# FPGA_Bypass_3V3.net
KiCad netlist of a schematic drawn in Altium Designer
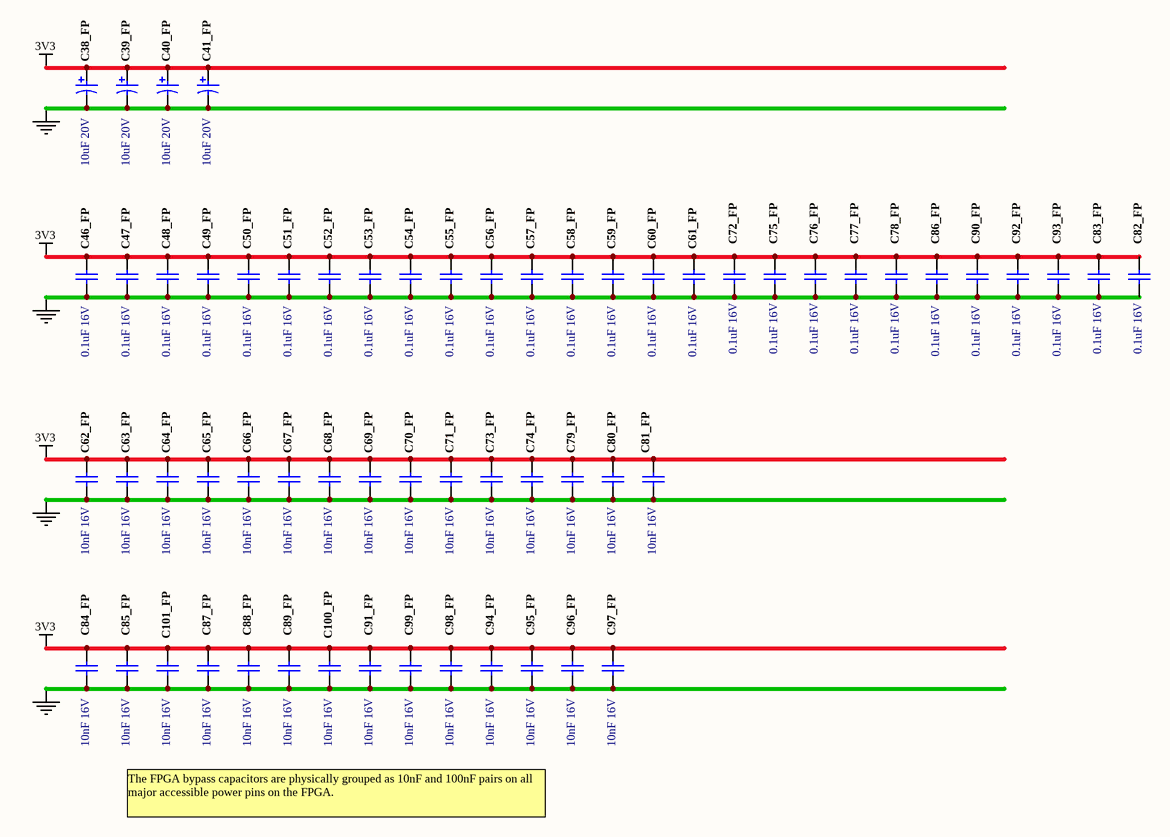
[diagram p0: FPGA_Bypass_3V3.SCHDOC]

(export (version "E")
  (design (tool "Eeschema 10.0.6"))
  (components
    (comp (ref "C38_FP")
      (value "10uF 20V")
      (footprint "CAPC3528-STAR")
      (description "Capacitor, Tantalum, 10uF 10% 20V MCCT-B (3528)")
      (fields (field (name "TOLERANCE") "10 %"))
      (libsource (lib "altium-import") (part "root_0_CAP-P_"))
    )
    (comp (ref "C39_FP")
      (value "10uF 20V")
      (footprint "CAPC3528-STAR")
      (description "Capacitor, Tantalum, 10uF 10% 20V MCCT-B (3528)")
      (fields (field (name "TOLERANCE") "10 %"))
      (libsource (lib "altium-import") (part "root_0_CAP-P_"))
    )
    (comp (ref "C40_FP")
      (value "10uF 20V")
      (footprint "CAPC3528-STAR")
      (description "Capacitor, Tantalum, 10uF 10% 20V MCCT-B (3528)")
      (fields (field (name "TOLERANCE") "10 %"))
      (libsource (lib "altium-import") (part "root_0_CAP-P_"))
    )
    (comp (ref "C41_FP")
      (value "10uF 20V")
      (footprint "CAPC3528-STAR")
      (description "Capacitor, Tantalum, 10uF 10% 20V MCCT-B (3528)")
      (fields (field (name "TOLERANCE") "10 %"))
      (libsource (lib "altium-import") (part "root_0_CAP-P_"))
    )
    (comp (ref "C46_FP")
      (value "0.1uF 16V")
      (footprint "CAPC1005-STAR")
      (description "Capacitor, Ceramic, 0.1uF 10% 16V 0402 (1005) X7R")
      (fields (field (name "TOLERANCE") "10 %"))
      (libsource (lib "altium-import") (part "root_0_mirrored_CAP-NP_"))
    )
    (comp (ref "C47_FP")
      (value "0.1uF 16V")
      (footprint "CAPC1005-STAR")
      (description "Capacitor, Ceramic, 0.1uF 10% 16V 0402 (1005) X7R")
      (fields (field (name "TOLERANCE") "10 %"))
      (libsource (lib "altium-import") (part "root_0_mirrored_CAP-NP_"))
    )
    (comp (ref "C48_FP")
      (value "0.1uF 16V")
      (footprint "CAPC1005-STAR")
      (description "Capacitor, Ceramic, 0.1uF 10% 16V 0402 (1005) X7R")
      (fields (field (name "TOLERANCE") "10 %"))
      (libsource (lib "altium-import") (part "root_0_mirrored_CAP-NP_"))
    )
    (comp (ref "C49_FP")
      (value "0.1uF 16V")
      (footprint "CAPC1005-STAR")
      (description "Capacitor, Ceramic, 0.1uF 10% 16V 0402 (1005) X7R")
      (fields (field (name "TOLERANCE") "10 %"))
      (libsource (lib "altium-import") (part "root_0_mirrored_CAP-NP_"))
    )
    (comp (ref "C50_FP")
      (value "0.1uF 16V")
      (footprint "CAPC1005-STAR")
      (description "Capacitor, Ceramic, 0.1uF 10% 16V 0402 (1005) X7R")
      (fields (field (name "TOLERANCE") "10 %"))
      (libsource (lib "altium-import") (part "root_0_mirrored_CAP-NP_"))
    )
    (comp (ref "C51_FP")
      (value "0.1uF 16V")
      (footprint "CAPC1005-STAR")
      (description "Capacitor, Ceramic, 0.1uF 10% 16V 0402 (1005) X7R")
      (fields (field (name "TOLERANCE") "10 %"))
      (libsource (lib "altium-import") (part "root_0_mirrored_CAP-NP_"))
    )
    (comp (ref "C52_FP")
      (value "0.1uF 16V")
      (footprint "CAPC1005-STAR")
      (description "Capacitor, Ceramic, 0.1uF 10% 16V 0402 (1005) X7R")
      (fields (field (name "TOLERANCE") "10 %"))
      (libsource (lib "altium-import") (part "root_0_mirrored_CAP-NP_"))
    )
    (comp (ref "C53_FP")
      (value "0.1uF 16V")
      (footprint "CAPC1005-STAR")
      (description "Capacitor, Ceramic, 0.1uF 10% 16V 0402 (1005) X7R")
      (fields (field (name "TOLERANCE") "10 %"))
      (libsource (lib "altium-import") (part "root_0_mirrored_CAP-NP_"))
    )
    (comp (ref "C54_FP")
      (value "0.1uF 16V")
      (footprint "CAPC1005-STAR")
      (description "Capacitor, Ceramic, 0.1uF 10% 16V 0402 (1005) X7R")
      (fields (field (name "TOLERANCE") "10 %"))
      (libsource (lib "altium-import") (part "root_0_mirrored_CAP-NP_"))
    )
    (comp (ref "C55_FP")
      (value "0.1uF 16V")
      (footprint "CAPC1005-STAR")
      (description "Capacitor, Ceramic, 0.1uF 10% 16V 0402 (1005) X7R")
      (fields (field (name "TOLERANCE") "10 %"))
      (libsource (lib "altium-import") (part "root_0_mirrored_CAP-NP_"))
    )
    (comp (ref "C56_FP")
      (value "0.1uF 16V")
      (footprint "CAPC1005-STAR")
      (description "Capacitor, Ceramic, 0.1uF 10% 16V 0402 (1005) X7R")
      (fields (field (name "TOLERANCE") "10 %"))
      (libsource (lib "altium-import") (part "root_0_mirrored_CAP-NP_"))
    )
    (comp (ref "C57_FP")
      (value "0.1uF 16V")
      (footprint "CAPC1005-STAR")
      (description "Capacitor, Ceramic, 0.1uF 10% 16V 0402 (1005) X7R")
      (fields (field (name "TOLERANCE") "10 %"))
      (libsource (lib "altium-import") (part "root_0_mirrored_CAP-NP_"))
    )
    (comp (ref "C58_FP")
      (value "0.1uF 16V")
      (footprint "CAPC1005-STAR")
      (description "Capacitor, Ceramic, 0.1uF 10% 16V 0402 (1005) X7R")
      (fields (field (name "TOLERANCE") "10 %"))
      (libsource (lib "altium-import") (part "root_0_mirrored_CAP-NP_"))
    )
    (comp (ref "C59_FP")
      (value "0.1uF 16V")
      (footprint "CAPC1005-STAR")
      (description "Capacitor, Ceramic, 0.1uF 10% 16V 0402 (1005) X7R")
      (fields (field (name "TOLERANCE") "10 %"))
      (libsource (lib "altium-import") (part "root_0_mirrored_CAP-NP_"))
    )
    (comp (ref "C60_FP")
      (value "0.1uF 16V")
      (footprint "CAPC1005-STAR")
      (description "Capacitor, Ceramic, 0.1uF 10% 16V 0402 (1005) X7R")
      (fields (field (name "TOLERANCE") "10 %"))
      (libsource (lib "altium-import") (part "root_0_mirrored_CAP-NP_"))
    )
    (comp (ref "C61_FP")
      (value "0.1uF 16V")
      (footprint "CAPC1005-STAR")
      (description "Capacitor, Ceramic, 0.1uF 10% 16V 0402 (1005) X7R")
      (fields (field (name "TOLERANCE") "10 %"))
      (libsource (lib "altium-import") (part "root_0_mirrored_CAP-NP_"))
    )
    (comp (ref "C62_FP")
      (value "10nF 16V")
      (footprint "CAPC1005-STAR")
      (description "Capacitor, Ceramic, 10nF 10% 16V 0402 (1005) X7R")
      (fields (field (name "TOLERANCE") "10 %"))
      (libsource (lib "altium-import") (part "root_0_CAP-NP_"))
    )
    (comp (ref "C63_FP")
      (value "10nF 16V")
      (footprint "CAPC1005-STAR")
      (description "Capacitor, Ceramic, 10nF 10% 16V 0402 (1005) X7R")
      (fields (field (name "TOLERANCE") "10 %"))
      (libsource (lib "altium-import") (part "root_0_CAP-NP_"))
    )
    (comp (ref "C64_FP")
      (value "10nF 16V")
      (footprint "CAPC1005-STAR")
      (description "Capacitor, Ceramic, 10nF 10% 16V 0402 (1005) X7R")
      (fields (field (name "TOLERANCE") "10 %"))
      (libsource (lib "altium-import") (part "root_0_CAP-NP_"))
    )
    (comp (ref "C65_FP")
      (value "10nF 16V")
      (footprint "CAPC1005-STAR")
      (description "Capacitor, Ceramic, 10nF 10% 16V 0402 (1005) X7R")
      (fields (field (name "TOLERANCE") "10 %"))
      (libsource (lib "altium-import") (part "root_0_CAP-NP_"))
    )
    (comp (ref "C66_FP")
      (value "10nF 16V")
      (footprint "CAPC1005-STAR")
      (description "Capacitor, Ceramic, 10nF 10% 16V 0402 (1005) X7R")
      (fields (field (name "TOLERANCE") "10 %"))
      (libsource (lib "altium-import") (part "root_0_CAP-NP_"))
    )
    (comp (ref "C67_FP")
      (value "10nF 16V")
      (footprint "CAPC1005-STAR")
      (description "Capacitor, Ceramic, 10nF 10% 16V 0402 (1005) X7R")
      (fields (field (name "TOLERANCE") "10 %"))
      (libsource (lib "altium-import") (part "root_0_CAP-NP_"))
    )
    (comp (ref "C68_FP")
      (value "10nF 16V")
      (footprint "CAPC1005-STAR")
      (description "Capacitor, Ceramic, 10nF 10% 16V 0402 (1005) X7R")
      (fields (field (name "TOLERANCE") "10 %"))
      (libsource (lib "altium-import") (part "root_0_CAP-NP_"))
    )
    (comp (ref "C69_FP")
      (value "10nF 16V")
      (footprint "CAPC1005-STAR")
      (description "Capacitor, Ceramic, 10nF 10% 16V 0402 (1005) X7R")
      (fields (field (name "TOLERANCE") "10 %"))
      (libsource (lib "altium-import") (part "root_0_CAP-NP_"))
    )
    (comp (ref "C70_FP")
      (value "10nF 16V")
      (footprint "CAPC1005-STAR")
      (description "Capacitor, Ceramic, 10nF 10% 16V 0402 (1005) X7R")
      (fields (field (name "TOLERANCE") "10 %"))
      (libsource (lib "altium-import") (part "root_0_CAP-NP_"))
    )
    (comp (ref "C71_FP")
      (value "10nF 16V")
      (footprint "CAPC1005-STAR")
      (description "Capacitor, Ceramic, 10nF 10% 16V 0402 (1005) X7R")
      (fields (field (name "TOLERANCE") "10 %"))
      (libsource (lib "altium-import") (part "root_0_CAP-NP_"))
    )
    (comp (ref "C72_FP")
      (value "0.1uF 16V")
      (footprint "CAPC1005-STAR")
      (description "Capacitor, Ceramic, 0.1uF 10% 16V 0402 (1005) X7R")
      (fields (field (name "TOLERANCE") "10 %"))
      (libsource (lib "AltiumDesignLibrary") (part "CAP-NP"))
    )
    (comp (ref "C73_FP")
      (value "10nF 16V")
      (footprint "CAPC1005-STAR")
      (description "Capacitor, Ceramic, 10nF 10% 16V 0402 (1005) X7R")
      (fields (field (name "TOLERANCE") "10 %"))
      (libsource (lib "altium-import") (part "root_0_CAP-NP_"))
    )
    (comp (ref "C74_FP")
      (value "10nF 16V")
      (footprint "CAPC1005-STAR")
      (description "Capacitor, Ceramic, 10nF 10% 16V 0402 (1005) X7R")
      (fields (field (name "TOLERANCE") "10 %"))
      (libsource (lib "altium-import") (part "root_0_CAP-NP_"))
    )
    (comp (ref "C75_FP")
      (value "0.1uF 16V")
      (footprint "CAPC1005-STAR")
      (description "Capacitor, Ceramic, 0.1uF 10% 16V 0402 (1005) X7R")
      (fields (field (name "TOLERANCE") "10 %"))
      (libsource (lib "AltiumDesignLibrary") (part "CAP-NP"))
    )
    (comp (ref "C76_FP")
      (value "0.1uF 16V")
      (footprint "CAPC1005-STAR")
      (description "Capacitor, Ceramic, 0.1uF 10% 16V 0402 (1005) X7R")
      (fields (field (name "TOLERANCE") "10 %"))
      (libsource (lib "AltiumDesignLibrary") (part "CAP-NP"))
    )
    (comp (ref "C77_FP")
      (value "0.1uF 16V")
      (footprint "CAPC1005-STAR")
      (description "Capacitor, Ceramic, 0.1uF 10% 16V 0402 (1005) X7R")
      (fields (field (name "TOLERANCE") "10 %"))
      (libsource (lib "AltiumDesignLibrary") (part "CAP-NP"))
    )
    (comp (ref "C78_FP")
      (value "0.1uF 16V")
      (footprint "CAPC1005-STAR")
      (description "Capacitor, Ceramic, 0.1uF 10% 16V 0402 (1005) X7R")
      (fields (field (name "TOLERANCE") "10 %"))
      (libsource (lib "AltiumDesignLibrary") (part "CAP-NP"))
    )
    (comp (ref "C79_FP")
      (value "10nF 16V")
      (footprint "CAPC1005-STAR")
      (description "Capacitor, Ceramic, 10nF 10% 16V 0402 (1005) X7R")
      (fields (field (name "TOLERANCE") "10 %"))
      (libsource (lib "altium-import") (part "root_0_CAP-NP_"))
    )
    (comp (ref "C80_FP")
      (value "10nF 16V")
      (footprint "CAPC1005-STAR")
      (description "Capacitor, Ceramic, 10nF 10% 16V 0402 (1005) X7R")
      (fields (field (name "TOLERANCE") "10 %"))
      (libsource (lib "altium-import") (part "root_0_CAP-NP_"))
    )
    (comp (ref "C81_FP")
      (value "10nF 16V")
      (footprint "CAPC1005-STAR")
      (description "Capacitor, Ceramic, 10nF 10% 16V 0402 (1005) X7R")
      (fields (field (name "TOLERANCE") "10 %"))
      (libsource (lib "altium-import") (part "root_0_CAP-NP_"))
    )
    (comp (ref "C82_FP")
      (value "0.1uF 16V")
      (footprint "CAPC1005-STAR")
      (description "Capacitor, Ceramic, 0.1uF 10% 16V 0402 (1005) X7R")
      (fields (field (name "TOLERANCE") "10 %"))
      (libsource (lib "AltiumDesignLibrary") (part "CAP-NP"))
    )
    (comp (ref "C83_FP")
      (value "0.1uF 16V")
      (footprint "CAPC1005-STAR")
      (description "Capacitor, Ceramic, 0.1uF 10% 16V 0402 (1005) X7R")
      (fields (field (name "TOLERANCE") "10 %"))
      (libsource (lib "AltiumDesignLibrary") (part "CAP-NP"))
    )
    (comp (ref "C84_FP")
      (value "10nF 16V")
      (footprint "CAPC1005-STAR")
      (description "Capacitor, Ceramic, 10nF 10% 16V 0402 (1005) X7R")
      (fields (field (name "TOLERANCE") "10 %"))
      (libsource (lib "altium-import") (part "root_0_CAP-NP_"))
    )
    (comp (ref "C85_FP")
      (value "10nF 16V")
      (footprint "CAPC1005-STAR")
      (description "Capacitor, Ceramic, 10nF 10% 16V 0402 (1005) X7R")
      (fields (field (name "TOLERANCE") "10 %"))
      (libsource (lib "altium-import") (part "root_0_CAP-NP_"))
    )
    (comp (ref "C86_FP")
      (value "0.1uF 16V")
      (footprint "CAPC1005-STAR")
      (description "Capacitor, Ceramic, 0.1uF 10% 16V 0402 (1005) X7R")
      (fields (field (name "TOLERANCE") "10 %"))
      (libsource (lib "AltiumDesignLibrary") (part "CAP-NP"))
    )
    (comp (ref "C87_FP")
      (value "10nF 16V")
      (footprint "CAPC1005-STAR")
      (description "Capacitor, Ceramic, 10nF 10% 16V 0402 (1005) X7R")
      (fields (field (name "TOLERANCE") "10 %"))
      (libsource (lib "altium-import") (part "root_0_CAP-NP_"))
    )
    (comp (ref "C88_FP")
      (value "10nF 16V")
      (footprint "CAPC1005-STAR")
      (description "Capacitor, Ceramic, 10nF 10% 16V 0402 (1005) X7R")
      (fields (field (name "TOLERANCE") "10 %"))
      (libsource (lib "altium-import") (part "root_0_CAP-NP_"))
    )
    (comp (ref "C89_FP")
      (value "10nF 16V")
      (footprint "CAPC1005-STAR")
      (description "Capacitor, Ceramic, 10nF 10% 16V 0402 (1005) X7R")
      (fields (field (name "TOLERANCE") "10 %"))
      (libsource (lib "altium-import") (part "root_0_CAP-NP_"))
    )
    (comp (ref "C90_FP")
      (value "0.1uF 16V")
      (footprint "CAPC1005-STAR")
      (description "Capacitor, Ceramic, 0.1uF 10% 16V 0402 (1005) X7R")
      (fields (field (name "TOLERANCE") "10 %"))
      (libsource (lib "AltiumDesignLibrary") (part "CAP-NP"))
    )
    (comp (ref "C91_FP")
      (value "10nF 16V")
      (footprint "CAPC1005-STAR")
      (description "Capacitor, Ceramic, 10nF 10% 16V 0402 (1005) X7R")
      (fields (field (name "TOLERANCE") "10 %"))
      (libsource (lib "altium-import") (part "root_0_CAP-NP_"))
    )
    (comp (ref "C92_FP")
      (value "0.1uF 16V")
      (footprint "CAPC1005-STAR")
      (description "Capacitor, Ceramic, 0.1uF 10% 16V 0402 (1005) X7R")
      (fields (field (name "TOLERANCE") "10 %"))
      (libsource (lib "AltiumDesignLibrary") (part "CAP-NP"))
    )
    (comp (ref "C93_FP")
      (value "0.1uF 16V")
      (footprint "CAPC1005-STAR")
      (description "Capacitor, Ceramic, 0.1uF 10% 16V 0402 (1005) X7R")
      (fields (field (name "TOLERANCE") "10 %"))
      (libsource (lib "AltiumDesignLibrary") (part "CAP-NP"))
    )
    (comp (ref "C94_FP")
      (value "10nF 16V")
      (footprint "CAPC1005-STAR")
      (description "Capacitor, Ceramic, 10nF 10% 16V 0402 (1005) X7R")
      (fields (field (name "TOLERANCE") "10 %"))
      (libsource (lib "altium-import") (part "root_0_CAP-NP_"))
    )
    (comp (ref "C95_FP")
      (value "10nF 16V")
      (footprint "CAPC1005-STAR")
      (description "Capacitor, Ceramic, 10nF 10% 16V 0402 (1005) X7R")
      (fields (field (name "TOLERANCE") "10 %"))
      (libsource (lib "altium-import") (part "root_0_CAP-NP_"))
    )
    (comp (ref "C96_FP")
      (value "10nF 16V")
      (footprint "CAPC1005-STAR")
      (description "Capacitor, Ceramic, 10nF 10% 16V 0402 (1005) X7R")
      (fields (field (name "TOLERANCE") "10 %"))
      (libsource (lib "altium-import") (part "root_0_CAP-NP_"))
    )
    (comp (ref "C97_FP")
      (value "10nF 16V")
      (footprint "CAPC1005-STAR")
      (description "Capacitor, Ceramic, 10nF 10% 16V 0402 (1005) X7R")
      (fields (field (name "TOLERANCE") "10 %"))
      (libsource (lib "altium-import") (part "root_0_CAP-NP_"))
    )
    (comp (ref "C98_FP")
      (value "10nF 16V")
      (footprint "CAPC1005-STAR")
      (description "Capacitor, Ceramic, 10nF 10% 16V 0402 (1005) X7R")
      (fields (field (name "TOLERANCE") "10 %"))
      (libsource (lib "altium-import") (part "root_0_CAP-NP_"))
    )
    (comp (ref "C99_FP")
      (value "10nF 16V")
      (footprint "CAPC1005-STAR")
      (description "Capacitor, Ceramic, 10nF 10% 16V 0402 (1005) X7R")
      (fields (field (name "TOLERANCE") "10 %"))
      (libsource (lib "altium-import") (part "root_0_CAP-NP_"))
    )
    (comp (ref "C100_FP")
      (value "10nF 16V")
      (footprint "CAPC1005-STAR")
      (description "Capacitor, Ceramic, 10nF 10% 16V 0402 (1005) X7R")
      (fields (field (name "TOLERANCE") "10 %"))
      (libsource (lib "altium-import") (part "root_0_CAP-NP_"))
    )
    (comp (ref "C101_FP")
      (value "10nF 16V")
      (footprint "CAPC1005-STAR")
      (description "Capacitor, Ceramic, 10nF 10% 16V 0402 (1005) X7R")
      (fields (field (name "TOLERANCE") "10 %"))
      (libsource (lib "altium-import") (part "root_0_CAP-NP_"))
    )
  )
  (nets
    (net (code "1") (name "3V3") (class "Default")
      (node (ref "C100_FP") (pin "1") (pinfunction "1_1") (pintype "passive"))
      (node (ref "C101_FP") (pin "1") (pinfunction "1_1") (pintype "passive"))
      (node (ref "C38_FP") (pin "1") (pinfunction "1_1") (pintype "passive"))
      (node (ref "C39_FP") (pin "1") (pinfunction "1_1") (pintype "passive"))
      (node (ref "C40_FP") (pin "1") (pinfunction "1_1") (pintype "passive"))
      (node (ref "C41_FP") (pin "1") (pinfunction "1_1") (pintype "passive"))
      (node (ref "C46_FP") (pin "1") (pinfunction "1_1") (pintype "passive"))
      (node (ref "C47_FP") (pin "1") (pinfunction "1_1") (pintype "passive"))
      (node (ref "C48_FP") (pin "1") (pinfunction "1_1") (pintype "passive"))
      (node (ref "C49_FP") (pin "1") (pinfunction "1_1") (pintype "passive"))
      (node (ref "C50_FP") (pin "1") (pinfunction "1_1") (pintype "passive"))
      (node (ref "C51_FP") (pin "1") (pinfunction "1_1") (pintype "passive"))
      (node (ref "C52_FP") (pin "1") (pinfunction "1_1") (pintype "passive"))
      (node (ref "C53_FP") (pin "1") (pinfunction "1_1") (pintype "passive"))
      (node (ref "C54_FP") (pin "1") (pinfunction "1_1") (pintype "passive"))
      (node (ref "C55_FP") (pin "1") (pinfunction "1_1") (pintype "passive"))
      (node (ref "C56_FP") (pin "1") (pinfunction "1_1") (pintype "passive"))
      (node (ref "C57_FP") (pin "1") (pinfunction "1_1") (pintype "passive"))
      (node (ref "C58_FP") (pin "1") (pinfunction "1_1") (pintype "passive"))
      (node (ref "C59_FP") (pin "1") (pinfunction "1_1") (pintype "passive"))
      (node (ref "C60_FP") (pin "1") (pinfunction "1_1") (pintype "passive"))
      (node (ref "C61_FP") (pin "1") (pinfunction "1_1") (pintype "passive"))
      (node (ref "C62_FP") (pin "1") (pinfunction "1_1") (pintype "passive"))
      (node (ref "C63_FP") (pin "1") (pinfunction "1_1") (pintype "passive"))
      (node (ref "C64_FP") (pin "1") (pinfunction "1_1") (pintype "passive"))
      (node (ref "C65_FP") (pin "1") (pinfunction "1_1") (pintype "passive"))
      (node (ref "C66_FP") (pin "1") (pinfunction "1_1") (pintype "passive"))
      (node (ref "C67_FP") (pin "1") (pinfunction "1_1") (pintype "passive"))
      (node (ref "C68_FP") (pin "1") (pinfunction "1_1") (pintype "passive"))
      (node (ref "C69_FP") (pin "1") (pinfunction "1_1") (pintype "passive"))
      (node (ref "C70_FP") (pin "1") (pinfunction "1_1") (pintype "passive"))
      (node (ref "C71_FP") (pin "1") (pinfunction "1_1") (pintype "passive"))
      (node (ref "C72_FP") (pin "1") (pinfunction "1_1") (pintype "passive"))
      (node (ref "C73_FP") (pin "1") (pinfunction "1_1") (pintype "passive"))
      (node (ref "C74_FP") (pin "1") (pinfunction "1_1") (pintype "passive"))
      (node (ref "C75_FP") (pin "1") (pinfunction "1_1") (pintype "passive"))
      (node (ref "C76_FP") (pin "1") (pinfunction "1_1") (pintype "passive"))
      (node (ref "C77_FP") (pin "1") (pinfunction "1_1") (pintype "passive"))
      (node (ref "C78_FP") (pin "1") (pinfunction "1_1") (pintype "passive"))
      (node (ref "C79_FP") (pin "1") (pinfunction "1_1") (pintype "passive"))
      (node (ref "C80_FP") (pin "1") (pinfunction "1_1") (pintype "passive"))
      (node (ref "C81_FP") (pin "1") (pinfunction "1_1") (pintype "passive"))
      (node (ref "C82_FP") (pin "1") (pinfunction "1_1") (pintype "passive"))
      (node (ref "C83_FP") (pin "1") (pinfunction "1_1") (pintype "passive"))
      (node (ref "C84_FP") (pin "1") (pinfunction "1_1") (pintype "passive"))
      (node (ref "C85_FP") (pin "1") (pinfunction "1_1") (pintype "passive"))
      (node (ref "C86_FP") (pin "1") (pinfunction "1_1") (pintype "passive"))
      (node (ref "C87_FP") (pin "1") (pinfunction "1_1") (pintype "passive"))
      (node (ref "C88_FP") (pin "1") (pinfunction "1_1") (pintype "passive"))
      (node (ref "C89_FP") (pin "1") (pinfunction "1_1") (pintype "passive"))
      (node (ref "C90_FP") (pin "1") (pinfunction "1_1") (pintype "passive"))
      (node (ref "C91_FP") (pin "1") (pinfunction "1_1") (pintype "passive"))
      (node (ref "C92_FP") (pin "1") (pinfunction "1_1") (pintype "passive"))
      (node (ref "C93_FP") (pin "1") (pinfunction "1_1") (pintype "passive"))
      (node (ref "C94_FP") (pin "1") (pinfunction "1_1") (pintype "passive"))
      (node (ref "C95_FP") (pin "1") (pinfunction "1_1") (pintype "passive"))
      (node (ref "C96_FP") (pin "1") (pinfunction "1_1") (pintype "passive"))
      (node (ref "C97_FP") (pin "1") (pinfunction "1_1") (pintype "passive"))
      (node (ref "C98_FP") (pin "1") (pinfunction "1_1") (pintype "passive"))
      (node (ref "C99_FP") (pin "1") (pinfunction "1_1") (pintype "passive"))
    )
    (net (code "2") (name "GND") (class "Default")
      (node (ref "C100_FP") (pin "2") (pinfunction "2_2") (pintype "passive"))
      (node (ref "C101_FP") (pin "2") (pinfunction "2_2") (pintype "passive"))
      (node (ref "C38_FP") (pin "2") (pinfunction "2_2") (pintype "passive"))
      (node (ref "C39_FP") (pin "2") (pinfunction "2_2") (pintype "passive"))
      (node (ref "C40_FP") (pin "2") (pinfunction "2_2") (pintype "passive"))
      (node (ref "C41_FP") (pin "2") (pinfunction "2_2") (pintype "passive"))
      (node (ref "C46_FP") (pin "2") (pinfunction "2_2") (pintype "passive"))
      (node (ref "C47_FP") (pin "2") (pinfunction "2_2") (pintype "passive"))
      (node (ref "C48_FP") (pin "2") (pinfunction "2_2") (pintype "passive"))
      (node (ref "C49_FP") (pin "2") (pinfunction "2_2") (pintype "passive"))
      (node (ref "C50_FP") (pin "2") (pinfunction "2_2") (pintype "passive"))
      (node (ref "C51_FP") (pin "2") (pinfunction "2_2") (pintype "passive"))
      (node (ref "C52_FP") (pin "2") (pinfunction "2_2") (pintype "passive"))
      (node (ref "C53_FP") (pin "2") (pinfunction "2_2") (pintype "passive"))
      (node (ref "C54_FP") (pin "2") (pinfunction "2_2") (pintype "passive"))
      (node (ref "C55_FP") (pin "2") (pinfunction "2_2") (pintype "passive"))
      (node (ref "C56_FP") (pin "2") (pinfunction "2_2") (pintype "passive"))
      (node (ref "C57_FP") (pin "2") (pinfunction "2_2") (pintype "passive"))
      (node (ref "C58_FP") (pin "2") (pinfunction "2_2") (pintype "passive"))
      (node (ref "C59_FP") (pin "2") (pinfunction "2_2") (pintype "passive"))
      (node (ref "C60_FP") (pin "2") (pinfunction "2_2") (pintype "passive"))
      (node (ref "C61_FP") (pin "2") (pinfunction "2_2") (pintype "passive"))
      (node (ref "C62_FP") (pin "2") (pinfunction "2_2") (pintype "passive"))
      (node (ref "C63_FP") (pin "2") (pinfunction "2_2") (pintype "passive"))
      (node (ref "C64_FP") (pin "2") (pinfunction "2_2") (pintype "passive"))
      (node (ref "C65_FP") (pin "2") (pinfunction "2_2") (pintype "passive"))
      (node (ref "C66_FP") (pin "2") (pinfunction "2_2") (pintype "passive"))
      (node (ref "C67_FP") (pin "2") (pinfunction "2_2") (pintype "passive"))
      (node (ref "C68_FP") (pin "2") (pinfunction "2_2") (pintype "passive"))
      (node (ref "C69_FP") (pin "2") (pinfunction "2_2") (pintype "passive"))
      (node (ref "C70_FP") (pin "2") (pinfunction "2_2") (pintype "passive"))
      (node (ref "C71_FP") (pin "2") (pinfunction "2_2") (pintype "passive"))
      (node (ref "C72_FP") (pin "2") (pinfunction "2_2") (pintype "passive"))
      (node (ref "C73_FP") (pin "2") (pinfunction "2_2") (pintype "passive"))
      (node (ref "C74_FP") (pin "2") (pinfunction "2_2") (pintype "passive"))
      (node (ref "C75_FP") (pin "2") (pinfunction "2_2") (pintype "passive"))
      (node (ref "C76_FP") (pin "2") (pinfunction "2_2") (pintype "passive"))
      (node (ref "C77_FP") (pin "2") (pinfunction "2_2") (pintype "passive"))
      (node (ref "C78_FP") (pin "2") (pinfunction "2_2") (pintype "passive"))
      (node (ref "C79_FP") (pin "2") (pinfunction "2_2") (pintype "passive"))
      (node (ref "C80_FP") (pin "2") (pinfunction "2_2") (pintype "passive"))
      (node (ref "C81_FP") (pin "2") (pinfunction "2_2") (pintype "passive"))
      (node (ref "C82_FP") (pin "2") (pinfunction "2_2") (pintype "passive"))
      (node (ref "C83_FP") (pin "2") (pinfunction "2_2") (pintype "passive"))
      (node (ref "C84_FP") (pin "2") (pinfunction "2_2") (pintype "passive"))
      (node (ref "C85_FP") (pin "2") (pinfunction "2_2") (pintype "passive"))
      (node (ref "C86_FP") (pin "2") (pinfunction "2_2") (pintype "passive"))
      (node (ref "C87_FP") (pin "2") (pinfunction "2_2") (pintype "passive"))
      (node (ref "C88_FP") (pin "2") (pinfunction "2_2") (pintype "passive"))
      (node (ref "C89_FP") (pin "2") (pinfunction "2_2") (pintype "passive"))
      (node (ref "C90_FP") (pin "2") (pinfunction "2_2") (pintype "passive"))
      (node (ref "C91_FP") (pin "2") (pinfunction "2_2") (pintype "passive"))
      (node (ref "C92_FP") (pin "2") (pinfunction "2_2") (pintype "passive"))
      (node (ref "C93_FP") (pin "2") (pinfunction "2_2") (pintype "passive"))
      (node (ref "C94_FP") (pin "2") (pinfunction "2_2") (pintype "passive"))
      (node (ref "C95_FP") (pin "2") (pinfunction "2_2") (pintype "passive"))
      (node (ref "C96_FP") (pin "2") (pinfunction "2_2") (pintype "passive"))
      (node (ref "C97_FP") (pin "2") (pinfunction "2_2") (pintype "passive"))
      (node (ref "C98_FP") (pin "2") (pinfunction "2_2") (pintype "passive"))
      (node (ref "C99_FP") (pin "2") (pinfunction "2_2") (pintype "passive"))
    )
  )
)
